# tuch-tara-tr.net
KiCad netlist of a schematic drawn in Altium Designer
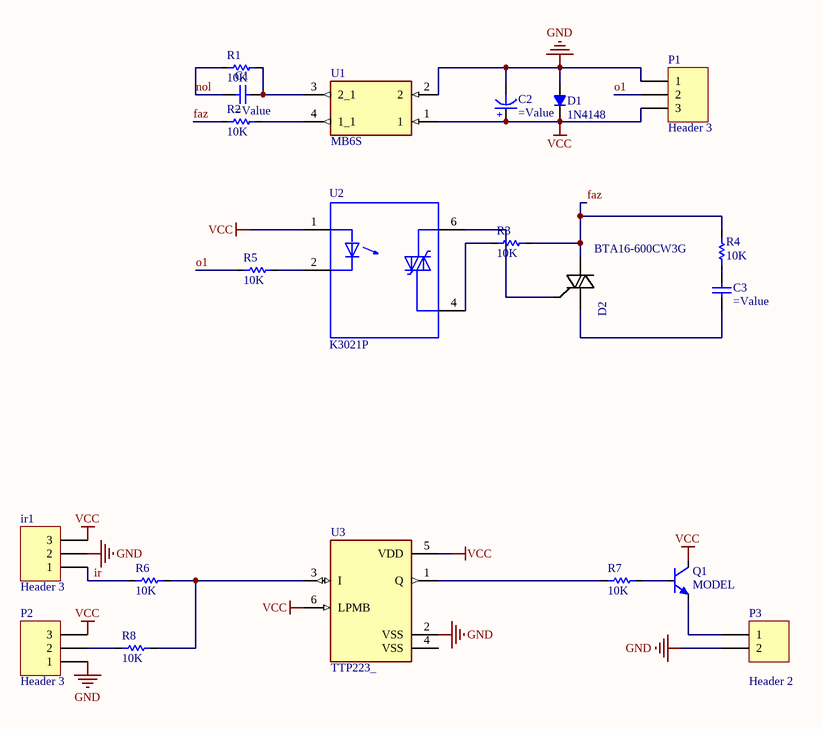
[diagram p0: tuch-tara-tr.SchDoc]

(export (version "E")
  (design (tool "Eeschema 10.0.6"))
  (components
    (comp (ref "C1")
      (value "~")
      (footprint "CAP-30")
      (description "Capacitor")
      (libsource (lib "AltiumLib1") (part "Capacitor"))
    )
    (comp (ref "C2")
      (value "~")
      (footprint "ELEC-CAP-RAD10-20")
      (description "Electrolytic Capacitor")
      (libsource (lib "AltiumLib1") (part "Capacitor Electrolytic"))
    )
    (comp (ref "C3")
      (value "~")
      (footprint "CAP-30")
      (description "Capacitor")
      (libsource (lib "AltiumLib1") (part "Capacitor"))
    )
    (comp (ref "D1")
      (value "MODEL")
      (footprint "DO-41")
      (description "Diode")
      (fields (field (name "MODEL") "1N4148"))
      (libsource (lib "AltiumLib1") (part "Diode"))
    )
    (comp (ref "D2")
      (value "BTA16-600CW3G")
      (footprint "*TO254P1028X482X1968-3")
      (description "TRIAC Standard 600V 16A Through Hole TO-220AB")
      (fields (field (name "MF") "Littelfuse Inc."))
      (libsource (lib "BTA16-600CW3G") (part "BTA16-600CW3G"))
    )
    (comp (ref "ir1")
      (value "Header 3")
      (footprint "HDR1X3")
      (description "Header, 3-Pin")
      (fields (field (name "PUBLISHER") "Altium Limited"))
      (libsource (lib "") (part "Header 3_1"))
    )
    (comp (ref "P1")
      (value "Header 3")
      (footprint "HDR1X3")
      (description "Header, 3-Pin")
      (fields (field (name "PUBLISHER") "Altium Limited"))
      (libsource (lib "Miscellaneous Connectors") (part "Header 3"))
    )
    (comp (ref "P2")
      (value "Header 3")
      (footprint "HDR1X3")
      (description "Header, 3-Pin")
      (fields (field (name "PUBLISHER") "Altium Limited"))
      (libsource (lib "") (part "Header 3_1"))
    )
    (comp (ref "P3")
      (value "Header 2")
      (footprint "HDR1X2")
      (description "Header, 2-Pin")
      (fields (field (name "PUBLISHER") "Altium Limited"))
      (libsource (lib "Miscellaneous Connectors") (part "Header 2"))
    )
    (comp (ref "Q1")
      (value "MODEL")
      (footprint "SOT32")
      (description "NPN Bipolar Transistor")
      (libsource (lib "AltiumLib1") (part "BD139"))
    )
    (comp (ref "R1")
      (value "10K")
      (footprint "Res-(1/4)")
      (description "Resistor")
      (fields (field (name "TOLERANCE") "5%") (field (name "POWER") "1/4 W"))
      (libsource (lib "AltiumLib1") (part "Resistor"))
    )
    (comp (ref "R2")
      (value "10K")
      (footprint "Res-(1/4)")
      (description "Resistor")
      (fields (field (name "TOLERANCE") "5%") (field (name "POWER") "1/4 W"))
      (libsource (lib "AltiumLib1") (part "Resistor"))
    )
    (comp (ref "R3")
      (value "10K")
      (footprint "RES 1206 (3216X08L)")
      (description "Resistor")
      (fields (field (name "TOLERANCE") "5%") (field (name "POWER") "1/4 W"))
      (libsource (lib "AltiumLib1") (part "Resistor"))
    )
    (comp (ref "R4")
      (value "10K")
      (footprint "RES 1206 (3216X08L)")
      (description "Resistor")
      (fields (field (name "TOLERANCE") "5%") (field (name "POWER") "1/4 W"))
      (libsource (lib "AltiumLib1") (part "Resistor"))
    )
    (comp (ref "R5")
      (value "10K")
      (footprint "RES 1206 (3216X08L)")
      (description "Resistor")
      (fields (field (name "TOLERANCE") "5%") (field (name "POWER") "1/4 W"))
      (libsource (lib "AltiumLib1") (part "Resistor"))
    )
    (comp (ref "R6")
      (value "10K")
      (footprint "RES 0805 (2012X06L)")
      (description "Resistor")
      (fields (field (name "TOLERANCE") "5%") (field (name "POWER") "1/4 W"))
      (libsource (lib "AltiumLib1") (part "Resistor"))
    )
    (comp (ref "R7")
      (value "10K")
      (footprint "RES 0805 (2012X06L)")
      (description "Resistor")
      (fields (field (name "TOLERANCE") "5%") (field (name "POWER") "1/4 W"))
      (libsource (lib "AltiumLib1") (part "Resistor"))
    )
    (comp (ref "R8")
      (value "10K")
      (footprint "RES 0805 (2012X06L)")
      (description "Resistor")
      (fields (field (name "TOLERANCE") "5%") (field (name "POWER") "1/4 W"))
      (libsource (lib "AltiumLib1") (part "Resistor"))
    )
    (comp (ref "U1")
      (value "MB6S")
      (footprint "SOIC245P670X270-4N")
      (description "Bridge Rectifier Single Phase Standard 600V Surface Mount 4-SOIC")
      (fields (field (name "MF") "ON Semiconductor") (field (name "DIGI-KEY_PART_NUMBER") "MB6SCT-ND"))
      (libsource (lib "MB6S") (part "MB6S"))
    )
    (comp (ref "U2")
      (value "K3021P")
      (footprint "DIP762W50P254L730H410Q6")
      (description "Optoisolator Triac Output 5300Vrms 1 Channel 6-DIP")
      (fields (field (name "MF") "Vishay Semiconductor"))
      (libsource (lib "K3021P") (part "K3021P"))
    )
    (comp (ref "U3")
      (value "TTP223_")
      (footprint "SOT95P285X126-6N")
      (fields (field (name "MP") "TTP223") (field (name "MF") "KOA Speer"))
      (libsource (lib "TTP223_") (part "TTP223_"))
    )
  )
  (nets
    (net (code "1") (name "/faz") (class "Default")
      (node (ref "D2") (pin "2") (pinfunction "MT2_2") (pintype "passive"))
      (node (ref "R2") (pin "2") (pinfunction "2_2") (pintype "passive"))
      (node (ref "R3") (pin "2") (pinfunction "2_2") (pintype "passive"))
      (node (ref "R4") (pin "2") (pinfunction "2_2") (pintype "passive"))
    )
    (net (code "2") (name "/ir") (class "Default")
      (node (ref "R6") (pin "1") (pinfunction "1_1") (pintype "passive"))
      (node (ref "ir1") (pin "1") (pinfunction "1_1") (pintype "passive"))
    )
    (net (code "3") (name "/nol") (class "Default")
      (node (ref "C1") (pin "1") (pinfunction "+_1") (pintype "passive"))
      (node (ref "R1") (pin "2") (pinfunction "2_2") (pintype "passive"))
    )
    (net (code "4") (name "/o1") (class "Default")
      (node (ref "P1") (pin "2") (pinfunction "2_2") (pintype "passive"))
      (node (ref "R5") (pin "1") (pinfunction "1_1") (pintype "passive"))
    )
    (net (code "5") (name "GND") (class "Default")
      (node (ref "C2") (pin "1") (pinfunction "-_1") (pintype "passive"))
      (node (ref "D1") (pin "1") (pinfunction "A_1") (pintype "passive"))
      (node (ref "P1") (pin "1") (pinfunction "1_1") (pintype "passive"))
      (node (ref "P2") (pin "1") (pinfunction "1_1") (pintype "passive"))
      (node (ref "P3") (pin "2") (pinfunction "2_2") (pintype "passive"))
      (node (ref "U1") (pin "2") (pinfunction "2_2") (pintype "input"))
      (node (ref "U3") (pin "2") (pinfunction "VSS_2") (pintype "power_in"))
      (node (ref "ir1") (pin "2") (pinfunction "2_2") (pintype "passive"))
    )
    (net (code "6") (name "Net-(C1--)") (class "Default")
      (node (ref "C1") (pin "2") (pinfunction "-_2") (pintype "passive"))
      (node (ref "R1") (pin "1") (pinfunction "1_1") (pintype "passive"))
      (node (ref "U1") (pin "3") (pinfunction "2_1_3") (pintype "output"))
    )
    (net (code "7") (name "Net-(C3-+)") (class "Default")
      (node (ref "C3") (pin "1") (pinfunction "+_1") (pintype "passive"))
      (node (ref "D2") (pin "1") (pinfunction "MT1_1") (pintype "passive"))
    )
    (net (code "8") (name "Net-(C3--)") (class "Default")
      (node (ref "C3") (pin "2") (pinfunction "-_2") (pintype "passive"))
      (node (ref "R4") (pin "1") (pinfunction "1_1") (pintype "passive"))
    )
    (net (code "9") (name "Net-(D2-G)") (class "Default")
      (node (ref "D2") (pin "3") (pinfunction "G_3") (pintype "passive"))
      (node (ref "U2") (pin "6") (pinfunction "MT2_6") (pintype "passive"))
    )
    (net (code "10") (name "Net-(P2-Pad2)") (class "Default")
      (node (ref "P2") (pin "2") (pinfunction "2_2") (pintype "passive"))
      (node (ref "R8") (pin "1") (pinfunction "1_1") (pintype "passive"))
    )
    (net (code "11") (name "Net-(Q1-B)") (class "Default")
      (node (ref "Q1") (pin "3") (pinfunction "B_3") (pintype "passive"))
      (node (ref "R7") (pin "2") (pinfunction "2_2") (pintype "passive"))
    )
    (net (code "12") (name "Net-(Q1-E)") (class "Default")
      (node (ref "P3") (pin "1") (pinfunction "1_1") (pintype "passive"))
      (node (ref "Q1") (pin "1") (pinfunction "E_1") (pintype "passive"))
    )
    (net (code "13") (name "Net-(U1-1_1)") (class "Default")
      (node (ref "R2") (pin "1") (pinfunction "1_1") (pintype "passive"))
      (node (ref "U1") (pin "4") (pinfunction "1_1_4") (pintype "output"))
    )
    (net (code "14") (name "Net-(U2-C)") (class "Default")
      (node (ref "R5") (pin "2") (pinfunction "2_2") (pintype "passive"))
      (node (ref "U2") (pin "2") (pinfunction "C_2") (pintype "passive"))
    )
    (net (code "15") (name "Net-(U2-MT1)") (class "Default")
      (node (ref "R3") (pin "1") (pinfunction "1_1") (pintype "passive"))
      (node (ref "U2") (pin "4") (pinfunction "MT1_4") (pintype "passive"))
    )
    (net (code "16") (name "Net-(U3-I)") (class "Default")
      (node (ref "R6") (pin "2") (pinfunction "2_2") (pintype "passive"))
      (node (ref "R8") (pin "2") (pinfunction "2_2") (pintype "passive"))
      (node (ref "U3") (pin "3") (pinfunction "I_3") (pintype "bidirectional"))
    )
    (net (code "17") (name "Net-(U3-Q)") (class "Default")
      (node (ref "R7") (pin "1") (pinfunction "1_1") (pintype "passive"))
      (node (ref "U3") (pin "1") (pinfunction "Q_1") (pintype "output"))
    )
    (net (code "18") (name "VCC") (class "Default")
      (node (ref "C2") (pin "2") (pinfunction "+_2") (pintype "passive"))
      (node (ref "D1") (pin "2") (pinfunction "K_2") (pintype "passive"))
      (node (ref "P1") (pin "3") (pinfunction "3_3") (pintype "passive"))
      (node (ref "P2") (pin "3") (pinfunction "3_3") (pintype "passive"))
      (node (ref "Q1") (pin "2") (pinfunction "C_2") (pintype "passive"))
      (node (ref "U1") (pin "1") (pinfunction "1_1") (pintype "input"))
      (node (ref "U2") (pin "1") (pinfunction "A_1") (pintype "passive"))
      (node (ref "U3") (pin "5") (pinfunction "VDD_5") (pintype "power_in"))
      (node (ref "U3") (pin "6") (pinfunction "LPMB_6") (pintype "input"))
      (node (ref "ir1") (pin "3") (pinfunction "3_3") (pintype "passive"))
    )
    (net (code "19") (name "unconnected-(U3-VSS-Pad4)") (class "Default")
      (node (ref "U3") (pin "4") (pinfunction "VSS_4") (pintype "power_in"))
    )
  )
)
